# Drone_SMD.net
KiCad netlist of a schematic drawn in EAGLE
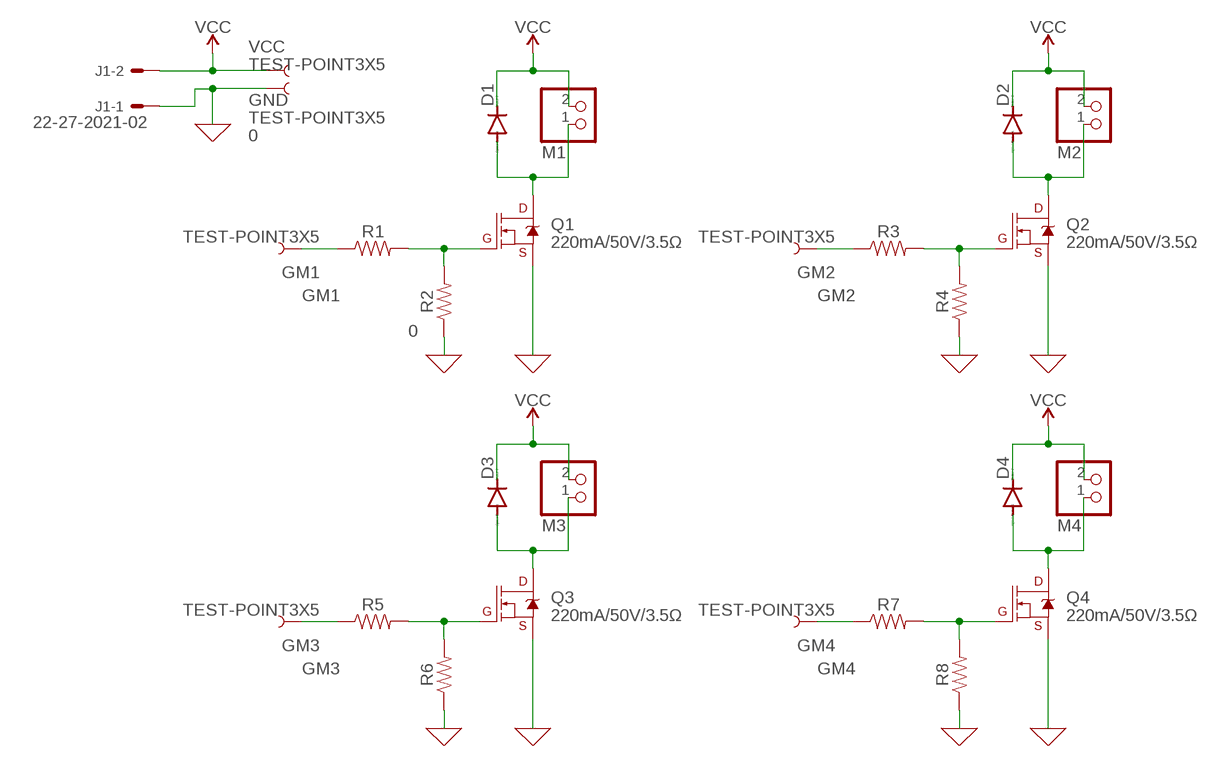
[diagram p0: schematic, sheet 1]

(export (version "E")
  (design (tool "Eeschema 10.0.6"))
  (components
    (comp (ref "D1")
      (value "DIODE-DO-214AC")
      (footprint "eagle-import:DO-214AC")
      (libsource (lib "eagle-import") (part "DIODE-DO-214AC"))
    )
    (comp (ref "D2")
      (value "DIODE-DO-214AC")
      (footprint "eagle-import:DO-214AC")
      (libsource (lib "eagle-import") (part "DIODE-DO-214AC"))
    )
    (comp (ref "D3")
      (value "DIODE-DO-214AC")
      (footprint "eagle-import:DO-214AC")
      (libsource (lib "eagle-import") (part "DIODE-DO-214AC"))
    )
    (comp (ref "D4")
      (value "DIODE-DO-214AC")
      (footprint "eagle-import:DO-214AC")
      (libsource (lib "eagle-import") (part "DIODE-DO-214AC"))
    )
    (comp (ref "GM1")
      (value "TEST-POINT3X5")
      (footprint "eagle-import:PAD.03X.05")
      (libsource (lib "eagle-import") (part "TEST-POINT3X5"))
    )
    (comp (ref "GM2")
      (value "TEST-POINT3X5")
      (footprint "eagle-import:PAD.03X.05")
      (libsource (lib "eagle-import") (part "TEST-POINT3X5"))
    )
    (comp (ref "GM3")
      (value "TEST-POINT3X5")
      (footprint "eagle-import:PAD.03X.05")
      (libsource (lib "eagle-import") (part "TEST-POINT3X5"))
    )
    (comp (ref "GM4")
      (value "TEST-POINT3X5")
      (footprint "eagle-import:PAD.03X.05")
      (libsource (lib "eagle-import") (part "TEST-POINT3X5"))
    )
    (comp (ref "GND")
      (value "TEST-POINT3X5")
      (footprint "eagle-import:PAD.03X.05")
      (libsource (lib "eagle-import") (part "TEST-POINT3X5"))
    )
    (comp (ref "J1")
      (value "22-27-2021-02")
      (footprint "eagle-import:6410-02")
      (fields (field (name "MF") "MOLEX"))
      (libsource (lib "eagle-import") (part "22-?-0227-2021"))
    )
    (comp (ref "M1")
      (value "PINHD-1X2")
      (footprint "eagle-import:1X02")
      (libsource (lib "eagle-import") (part "PINHD-1X2"))
    )
    (comp (ref "M2")
      (value "PINHD-1X2")
      (footprint "eagle-import:1X02")
      (libsource (lib "eagle-import") (part "PINHD-1X2"))
    )
    (comp (ref "M3")
      (value "PINHD-1X2")
      (footprint "eagle-import:1X02")
      (libsource (lib "eagle-import") (part "PINHD-1X2"))
    )
    (comp (ref "M4")
      (value "PINHD-1X2")
      (footprint "eagle-import:1X02")
      (libsource (lib "eagle-import") (part "PINHD-1X2"))
    )
    (comp (ref "Q1")
      (value "220mA/50V/3.5Ω")
      (footprint "eagle-import:SOT23-3")
      (libsource (lib "eagle-import") (part "MOSFET-NCH-BSS138"))
    )
    (comp (ref "Q2")
      (value "220mA/50V/3.5Ω")
      (footprint "eagle-import:SOT23-3")
      (libsource (lib "eagle-import") (part "MOSFET-NCH-BSS138"))
    )
    (comp (ref "Q3")
      (value "220mA/50V/3.5Ω")
      (footprint "eagle-import:SOT23-3")
      (libsource (lib "eagle-import") (part "MOSFET-NCH-BSS138"))
    )
    (comp (ref "Q4")
      (value "220mA/50V/3.5Ω")
      (footprint "eagle-import:SOT23-3")
      (libsource (lib "eagle-import") (part "MOSFET-NCH-BSS138"))
    )
    (comp (ref "R1")
      (value "RESISTOR1206")
      (footprint "eagle-import:1206")
      (libsource (lib "eagle-import") (part "RESISTOR1206"))
    )
    (comp (ref "R2")
      (value "RESISTOR1206")
      (footprint "eagle-import:1206")
      (libsource (lib "eagle-import") (part "RESISTOR1206"))
    )
    (comp (ref "R3")
      (value "RESISTOR1206")
      (footprint "eagle-import:1206")
      (libsource (lib "eagle-import") (part "RESISTOR1206"))
    )
    (comp (ref "R4")
      (value "RESISTOR1206")
      (footprint "eagle-import:1206")
      (libsource (lib "eagle-import") (part "RESISTOR1206"))
    )
    (comp (ref "R5")
      (value "RESISTOR1206")
      (footprint "eagle-import:1206")
      (libsource (lib "eagle-import") (part "RESISTOR1206"))
    )
    (comp (ref "R6")
      (value "RESISTOR1206")
      (footprint "eagle-import:1206")
      (libsource (lib "eagle-import") (part "RESISTOR1206"))
    )
    (comp (ref "R7")
      (value "RESISTOR1206")
      (footprint "eagle-import:1206")
      (libsource (lib "eagle-import") (part "RESISTOR1206"))
    )
    (comp (ref "R8")
      (value "RESISTOR1206")
      (footprint "eagle-import:1206")
      (libsource (lib "eagle-import") (part "RESISTOR1206"))
    )
    (comp (ref "VCC")
      (value "TEST-POINT3X5")
      (footprint "eagle-import:PAD.03X.05")
      (libsource (lib "eagle-import") (part "TEST-POINT3X5"))
    )
  )
  (nets
    (net (code "1") (name "/GM1") (class "Default")
      (node (ref "GM1") (pin "1") (pinfunction "1_1") (pintype "bidirectional"))
      (node (ref "R1") (pin "1") (pinfunction "1_1") (pintype "passive"))
    )
    (net (code "2") (name "/GM2") (class "Default")
      (node (ref "GM2") (pin "1") (pinfunction "1_1") (pintype "bidirectional"))
      (node (ref "R3") (pin "1") (pinfunction "1_1") (pintype "passive"))
    )
    (net (code "3") (name "/GM3") (class "Default")
      (node (ref "GM3") (pin "1") (pinfunction "1_1") (pintype "bidirectional"))
      (node (ref "R5") (pin "1") (pinfunction "1_1") (pintype "passive"))
    )
    (net (code "4") (name "/GM4") (class "Default")
      (node (ref "GM4") (pin "1") (pinfunction "1_1") (pintype "bidirectional"))
      (node (ref "R7") (pin "1") (pinfunction "1_1") (pintype "passive"))
    )
    (net (code "5") (name "GND") (class "Default")
      (node (ref "GND") (pin "1") (pinfunction "1_1") (pintype "bidirectional"))
      (node (ref "J1") (pin "1") (pinfunction "S_1") (pintype "passive"))
      (node (ref "Q1") (pin "2") (pinfunction "S_2") (pintype "bidirectional"))
      (node (ref "Q2") (pin "2") (pinfunction "S_2") (pintype "bidirectional"))
      (node (ref "Q3") (pin "2") (pinfunction "S_2") (pintype "bidirectional"))
      (node (ref "Q4") (pin "2") (pinfunction "S_2") (pintype "bidirectional"))
      (node (ref "R2") (pin "1") (pinfunction "1_1") (pintype "passive"))
      (node (ref "R4") (pin "1") (pinfunction "1_1") (pintype "passive"))
      (node (ref "R6") (pin "1") (pinfunction "1_1") (pintype "passive"))
      (node (ref "R8") (pin "1") (pinfunction "1_1") (pintype "passive"))
    )
    (net (code "6") (name "Net-(Q1-D)") (class "Default")
      (node (ref "D1") (pin "A") (pinfunction "A_A") (pintype "passive"))
      (node (ref "M1") (pin "1") (pinfunction "1_1") (pintype "passive"))
      (node (ref "Q1") (pin "3") (pinfunction "D_3") (pintype "bidirectional"))
    )
    (net (code "7") (name "Net-(Q1-G)") (class "Default")
      (node (ref "Q1") (pin "1") (pinfunction "G_1") (pintype "bidirectional"))
      (node (ref "R1") (pin "2") (pinfunction "2_2") (pintype "passive"))
      (node (ref "R2") (pin "2") (pinfunction "2_2") (pintype "passive"))
    )
    (net (code "8") (name "Net-(Q2-D)") (class "Default")
      (node (ref "D2") (pin "A") (pinfunction "A_A") (pintype "passive"))
      (node (ref "M2") (pin "1") (pinfunction "1_1") (pintype "passive"))
      (node (ref "Q2") (pin "3") (pinfunction "D_3") (pintype "bidirectional"))
    )
    (net (code "9") (name "Net-(Q2-G)") (class "Default")
      (node (ref "Q2") (pin "1") (pinfunction "G_1") (pintype "bidirectional"))
      (node (ref "R3") (pin "2") (pinfunction "2_2") (pintype "passive"))
      (node (ref "R4") (pin "2") (pinfunction "2_2") (pintype "passive"))
    )
    (net (code "10") (name "Net-(Q3-D)") (class "Default")
      (node (ref "D3") (pin "A") (pinfunction "A_A") (pintype "passive"))
      (node (ref "M3") (pin "1") (pinfunction "1_1") (pintype "passive"))
      (node (ref "Q3") (pin "3") (pinfunction "D_3") (pintype "bidirectional"))
    )
    (net (code "11") (name "Net-(Q3-G)") (class "Default")
      (node (ref "Q3") (pin "1") (pinfunction "G_1") (pintype "bidirectional"))
      (node (ref "R5") (pin "2") (pinfunction "2_2") (pintype "passive"))
      (node (ref "R6") (pin "2") (pinfunction "2_2") (pintype "passive"))
    )
    (net (code "12") (name "Net-(Q4-D)") (class "Default")
      (node (ref "D4") (pin "A") (pinfunction "A_A") (pintype "passive"))
      (node (ref "M4") (pin "1") (pinfunction "1_1") (pintype "passive"))
      (node (ref "Q4") (pin "3") (pinfunction "D_3") (pintype "bidirectional"))
    )
    (net (code "13") (name "Net-(Q4-G)") (class "Default")
      (node (ref "Q4") (pin "1") (pinfunction "G_1") (pintype "bidirectional"))
      (node (ref "R7") (pin "2") (pinfunction "2_2") (pintype "passive"))
      (node (ref "R8") (pin "2") (pinfunction "2_2") (pintype "passive"))
    )
    (net (code "14") (name "VCC") (class "Default")
      (node (ref "D1") (pin "C") (pinfunction "C_C") (pintype "passive"))
      (node (ref "D2") (pin "C") (pinfunction "C_C") (pintype "passive"))
      (node (ref "D3") (pin "C") (pinfunction "C_C") (pintype "passive"))
      (node (ref "D4") (pin "C") (pinfunction "C_C") (pintype "passive"))
      (node (ref "J1") (pin "2") (pinfunction "S_2") (pintype "passive"))
      (node (ref "M1") (pin "2") (pinfunction "2_2") (pintype "passive"))
      (node (ref "M2") (pin "2") (pinfunction "2_2") (pintype "passive"))
      (node (ref "M3") (pin "2") (pinfunction "2_2") (pintype "passive"))
      (node (ref "M4") (pin "2") (pinfunction "2_2") (pintype "passive"))
      (node (ref "VCC") (pin "1") (pinfunction "1_1") (pintype "bidirectional"))
    )
  )
)
